# tricorder-featherwing-mk-1_7.net
KiCad netlist of a schematic drawn in EAGLE
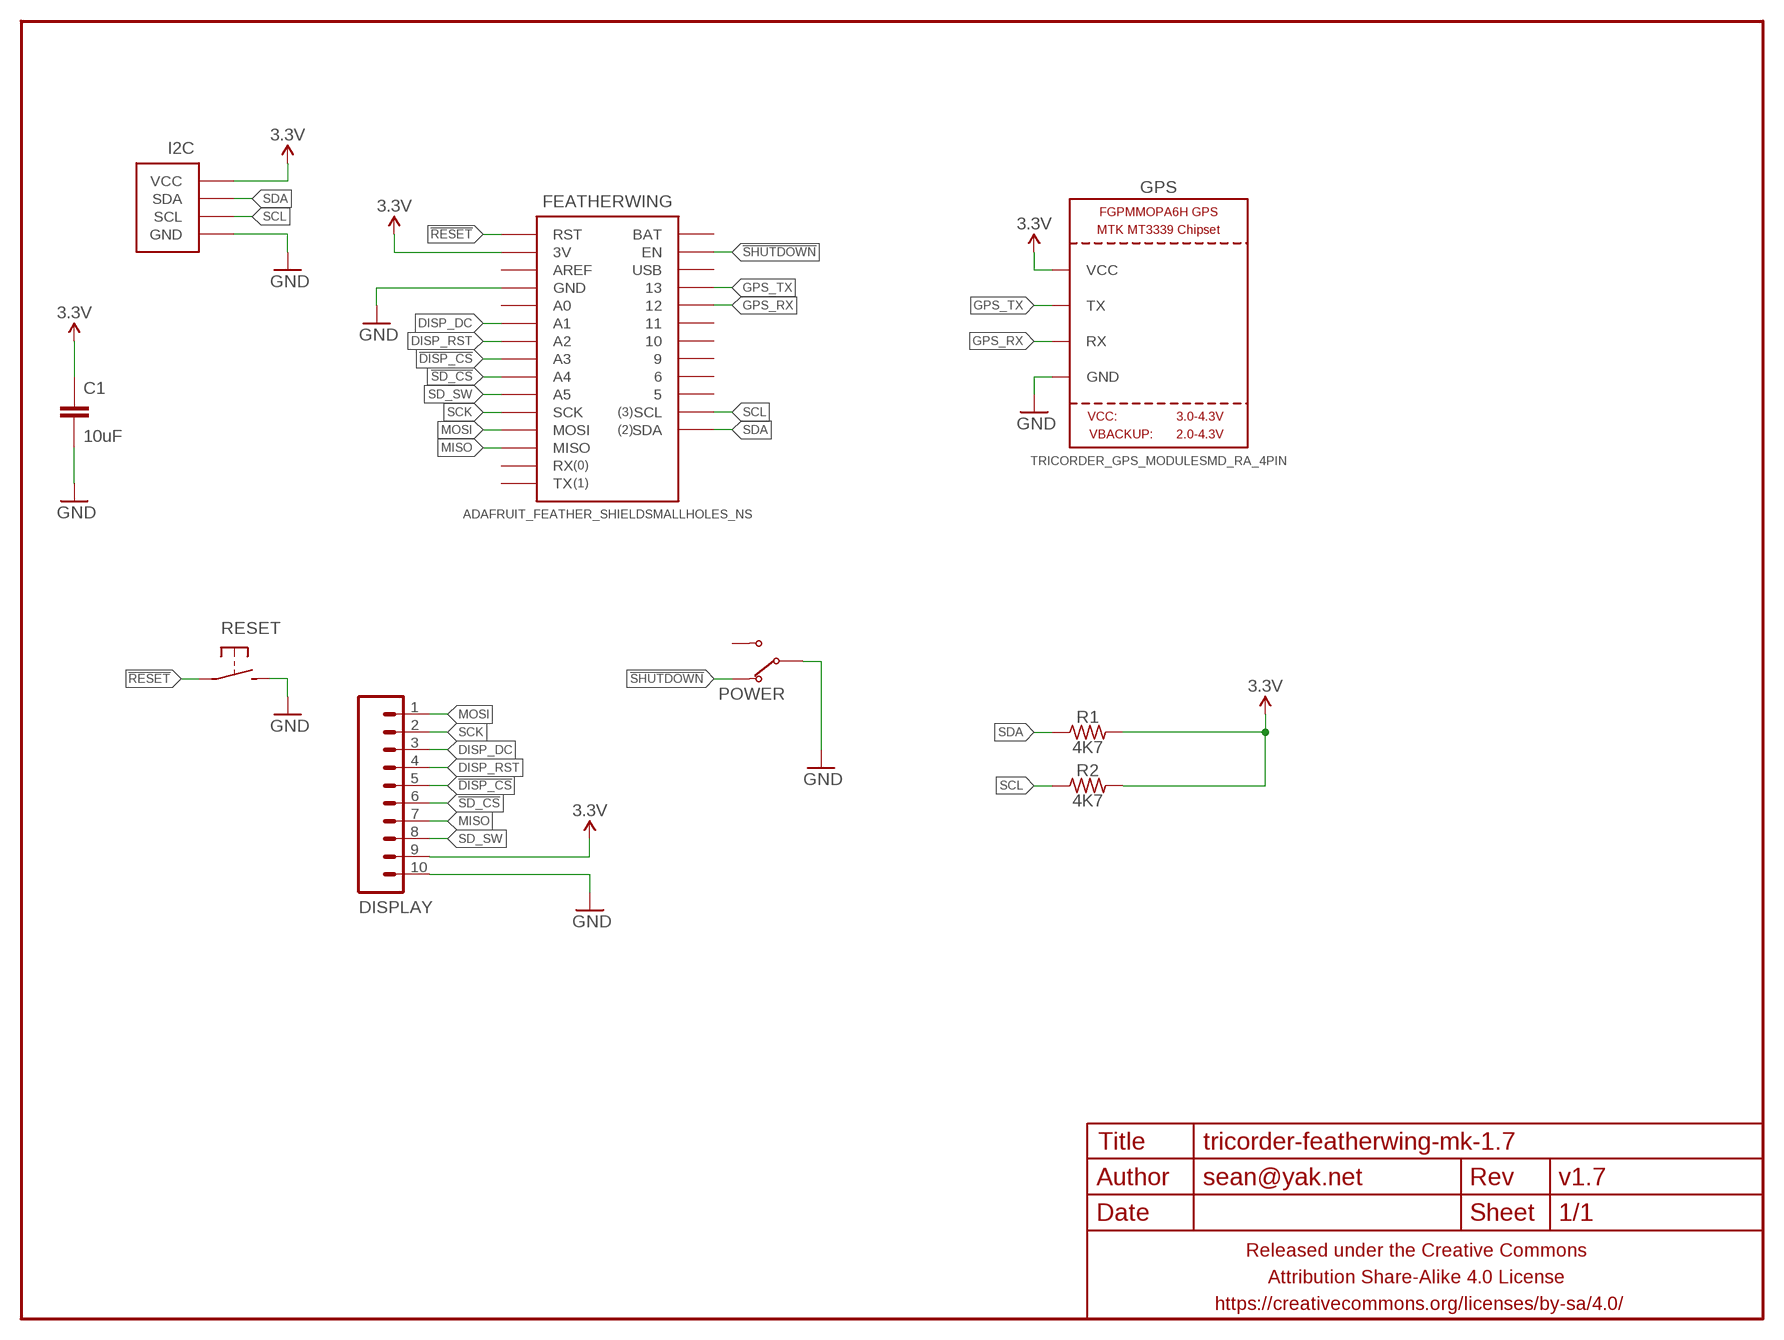
[diagram p0: schematic, sheet 1]

(export (version "E")
  (design (tool "Eeschema 10.0.6"))
  (components
    (comp (ref "C1")
      (value "10uF")
      (footprint "eagle-import:C1210")
      (libsource (lib "eagle-import") (part "CAPACITOR-CERAMICC1210"))
    )
    (comp (ref "DISPLAY")
      (value "M102MM")
      (footprint "eagle-import:1X10-2MM")
      (libsource (lib "eagle-import") (part "M102MM"))
    )
    (comp (ref "FEATHERWING")
      (value "ADAFRUIT_FEATHER_SHIELDSMALLHOLES_NS")
      (footprint "eagle-import:ADAFRUIT_FEATHER_SMALLHOLES_NS")
      (libsource (lib "eagle-import") (part "ADAFRUIT_FEATHER_SHIELDSMALLHOLES_NS"))
    )
    (comp (ref "FRAME1")
      (value "FRAME-LETTERNO_PACKAGE")
      (footprint "eagle-import:DUMMY")
      (fields (field (name "DESIGNER") "sean@yak.net") (field (name "VERSION") "v1.7"))
      (libsource (lib "eagle-import") (part "FRAME-LETTERNO_PACKAGE"))
    )
    (comp (ref "GPS")
      (value "TRICORDER_GPS_MODULESMD_RA_4PIN")
      (footprint "eagle-import:TRICORDER_GPS_MODULE_RA_CONN_SMD_4PIN")
      (libsource (lib "eagle-import") (part "TRICORDER_GPS_MODULESMD_RA_4PIN"))
    )
    (comp (ref "I2C")
      (value "M04-I2CPTH-2MM-CENTERED")
      (footprint "eagle-import:1X04-2MM-CENTERED-I2C")
      (libsource (lib "eagle-import") (part "M04-I2CPTH-2MM-CENTERED"))
    )
    (comp (ref "POWER")
      (value "SWITCH-SPDTPTH-RA-2.54MM-CENTERED")
      (footprint "eagle-import:SPDT-RA-2.54MM-CENTERED")
      (libsource (lib "eagle-import") (part "SWITCH-SPDTPTH-RA-2.54MM-CENTERED"))
    )
    (comp (ref "R1")
      (value "4K7")
      (footprint "eagle-import:R0603")
      (libsource (lib "eagle-import") (part "RESISTORR0603"))
    )
    (comp (ref "R2")
      (value "4K7")
      (footprint "eagle-import:R0603")
      (libsource (lib "eagle-import") (part "RESISTORR0603"))
    )
    (comp (ref "RESET")
      (value "SPST-NO-TACTCK-PTS840-GK")
      (footprint "eagle-import:TACTILE-SMD-CK-PTS840-GK")
      (libsource (lib "eagle-import") (part "SPST-NO-TACTCK-PTS840-GK"))
    )
  )
  (nets
    (net (code "1") (name "/~{DISP_CS}") (class "Default")
      (node (ref "DISPLAY") (pin "5") (pinfunction "5_5") (pintype "passive"))
      (node (ref "FEATHERWING") (pin "A3") (pinfunction "A3_A3") (pintype "bidirectional"))
    )
    (net (code "2") (name "/~{RESET}") (class "Default")
      (node (ref "FEATHERWING") (pin "RST") (pinfunction "RST_RST") (pintype "bidirectional"))
      (node (ref "RESET") (pin "1") (pinfunction "1_1") (pintype "passive"))
      (node (ref "RESET") (pin "2") (pinfunction "1_2") (pintype "passive"))
    )
    (net (code "3") (name "/~{SD_CS}") (class "Default")
      (node (ref "DISPLAY") (pin "6") (pinfunction "6_6") (pintype "passive"))
      (node (ref "FEATHERWING") (pin "A4") (pinfunction "A4_A4") (pintype "bidirectional"))
    )
    (net (code "4") (name "/~{SHUTDOWN}") (class "Default")
      (node (ref "FEATHERWING") (pin "EN") (pinfunction "EN_EN") (pintype "bidirectional"))
      (node (ref "POWER") (pin "1") (pinfunction "NC_1") (pintype "passive"))
    )
    (net (code "5") (name "3.3V") (class "Default")
      (node (ref "C1") (pin "1") (pinfunction "1_1") (pintype "passive"))
      (node (ref "DISPLAY") (pin "9") (pinfunction "9_9") (pintype "passive"))
      (node (ref "FEATHERWING") (pin "3V") (pinfunction "3V_3V") (pintype "bidirectional"))
      (node (ref "GPS") (pin "VCC") (pinfunction "VCC_VCC") (pintype "bidirectional"))
      (node (ref "I2C") (pin "2") (pinfunction "VCC_2") (pintype "bidirectional"))
      (node (ref "R1") (pin "2") (pinfunction "2_2") (pintype "passive"))
      (node (ref "R2") (pin "2") (pinfunction "2_2") (pintype "passive"))
    )
    (net (code "6") (name "DISP_DC") (class "Default")
      (node (ref "DISPLAY") (pin "3") (pinfunction "3_3") (pintype "passive"))
      (node (ref "FEATHERWING") (pin "A1") (pinfunction "A1_A1") (pintype "bidirectional"))
    )
    (net (code "7") (name "DISP_RST") (class "Default")
      (node (ref "DISPLAY") (pin "4") (pinfunction "4_4") (pintype "passive"))
      (node (ref "FEATHERWING") (pin "A2") (pinfunction "A2_A2") (pintype "bidirectional"))
    )
    (net (code "8") (name "GND") (class "Default")
      (node (ref "C1") (pin "2") (pinfunction "2_2") (pintype "passive"))
      (node (ref "DISPLAY") (pin "10") (pinfunction "10_10") (pintype "passive"))
      (node (ref "FEATHERWING") (pin "GND@0") (pinfunction "GND_GND@0") (pintype "bidirectional"))
      (node (ref "FEATHERWING") (pin "GND@1") (pinfunction "GND_GND@1") (pintype "bidirectional"))
      (node (ref "GPS") (pin "GND") (pinfunction "GND_GND") (pintype "bidirectional"))
      (node (ref "I2C") (pin "1") (pinfunction "GND_1") (pintype "bidirectional"))
      (node (ref "POWER") (pin "2") (pinfunction "COM_2") (pintype "passive"))
      (node (ref "RESET") (pin "3") (pinfunction "2_3") (pintype "passive"))
      (node (ref "RESET") (pin "4") (pinfunction "2_4") (pintype "passive"))
    )
    (net (code "9") (name "GPS_RX") (class "Default")
      (node (ref "FEATHERWING") (pin "12") (pinfunction "12_12") (pintype "bidirectional"))
      (node (ref "GPS") (pin "RX") (pinfunction "RX_RX") (pintype "bidirectional"))
    )
    (net (code "10") (name "GPS_TX") (class "Default")
      (node (ref "FEATHERWING") (pin "13") (pinfunction "13_13") (pintype "bidirectional"))
      (node (ref "GPS") (pin "TX") (pinfunction "TX_TX") (pintype "bidirectional"))
    )
    (net (code "11") (name "MISO") (class "Default")
      (node (ref "DISPLAY") (pin "7") (pinfunction "7_7") (pintype "passive"))
      (node (ref "FEATHERWING") (pin "MISO") (pinfunction "MISO_MISO") (pintype "bidirectional"))
    )
    (net (code "12") (name "MOSI") (class "Default")
      (node (ref "DISPLAY") (pin "1") (pinfunction "1_1") (pintype "passive"))
      (node (ref "FEATHERWING") (pin "MOSI") (pinfunction "MOSI_MOSI") (pintype "bidirectional"))
    )
    (net (code "13") (name "SCK") (class "Default")
      (node (ref "DISPLAY") (pin "2") (pinfunction "2_2") (pintype "passive"))
      (node (ref "FEATHERWING") (pin "SCK") (pinfunction "SCK_SCK") (pintype "bidirectional"))
    )
    (net (code "14") (name "SCL") (class "Default")
      (node (ref "FEATHERWING") (pin "SCL") (pinfunction "SCL_SCL") (pintype "bidirectional"))
      (node (ref "I2C") (pin "4") (pinfunction "SCL_4") (pintype "bidirectional"))
      (node (ref "R2") (pin "1") (pinfunction "1_1") (pintype "passive"))
    )
    (net (code "15") (name "SDA") (class "Default")
      (node (ref "FEATHERWING") (pin "SDA") (pinfunction "SDA_SDA") (pintype "bidirectional"))
      (node (ref "I2C") (pin "3") (pinfunction "SDA_3") (pintype "bidirectional"))
      (node (ref "R1") (pin "1") (pinfunction "1_1") (pintype "passive"))
    )
    (net (code "16") (name "SD_SW") (class "Default")
      (node (ref "DISPLAY") (pin "8") (pinfunction "8_8") (pintype "passive"))
      (node (ref "FEATHERWING") (pin "A5") (pinfunction "A5_A5") (pintype "bidirectional"))
    )
    (net (code "17") (name "unconnected-(FEATHERWING-Pad5)") (class "Default")
      (node (ref "FEATHERWING") (pin "5") (pinfunction "5_5") (pintype "bidirectional"))
    )
    (net (code "18") (name "unconnected-(FEATHERWING-Pad6)") (class "Default")
      (node (ref "FEATHERWING") (pin "6") (pinfunction "6_6") (pintype "bidirectional"))
    )
    (net (code "19") (name "unconnected-(FEATHERWING-Pad9)") (class "Default")
      (node (ref "FEATHERWING") (pin "9") (pinfunction "9_9") (pintype "bidirectional"))
    )
    (net (code "20") (name "unconnected-(FEATHERWING-Pad10)") (class "Default")
      (node (ref "FEATHERWING") (pin "10") (pinfunction "10_10") (pintype "bidirectional"))
    )
    (net (code "21") (name "unconnected-(FEATHERWING-Pad11)") (class "Default")
      (node (ref "FEATHERWING") (pin "11") (pinfunction "11_11") (pintype "bidirectional"))
    )
    (net (code "22") (name "unconnected-(FEATHERWING-PadA0)") (class "Default")
      (node (ref "FEATHERWING") (pin "A0") (pinfunction "A0_A0") (pintype "bidirectional"))
    )
    (net (code "23") (name "unconnected-(FEATHERWING-PadAREF)") (class "Default")
      (node (ref "FEATHERWING") (pin "AREF") (pinfunction "AREF_AREF") (pintype "bidirectional"))
    )
    (net (code "24") (name "unconnected-(FEATHERWING-PadBAT)") (class "Default")
      (node (ref "FEATHERWING") (pin "BAT") (pinfunction "BAT_BAT") (pintype "bidirectional"))
    )
    (net (code "25") (name "unconnected-(FEATHERWING-PadRX)") (class "Default")
      (node (ref "FEATHERWING") (pin "RX") (pinfunction "RX_RX") (pintype "bidirectional"))
    )
    (net (code "26") (name "unconnected-(FEATHERWING-PadTX)") (class "Default")
      (node (ref "FEATHERWING") (pin "TX") (pinfunction "TX_TX") (pintype "bidirectional"))
    )
    (net (code "27") (name "unconnected-(FEATHERWING-PadUSB)") (class "Default")
      (node (ref "FEATHERWING") (pin "USB") (pinfunction "USB_USB") (pintype "bidirectional"))
    )
    (net (code "28") (name "unconnected-(POWER-NO-Pad3)") (class "Default")
      (node (ref "POWER") (pin "3") (pinfunction "NO_3") (pintype "passive"))
    )
  )
)
